# SCH_RejsaCAN_v3_4.net
KiCad netlist of a schematic drawn in EasyEDA
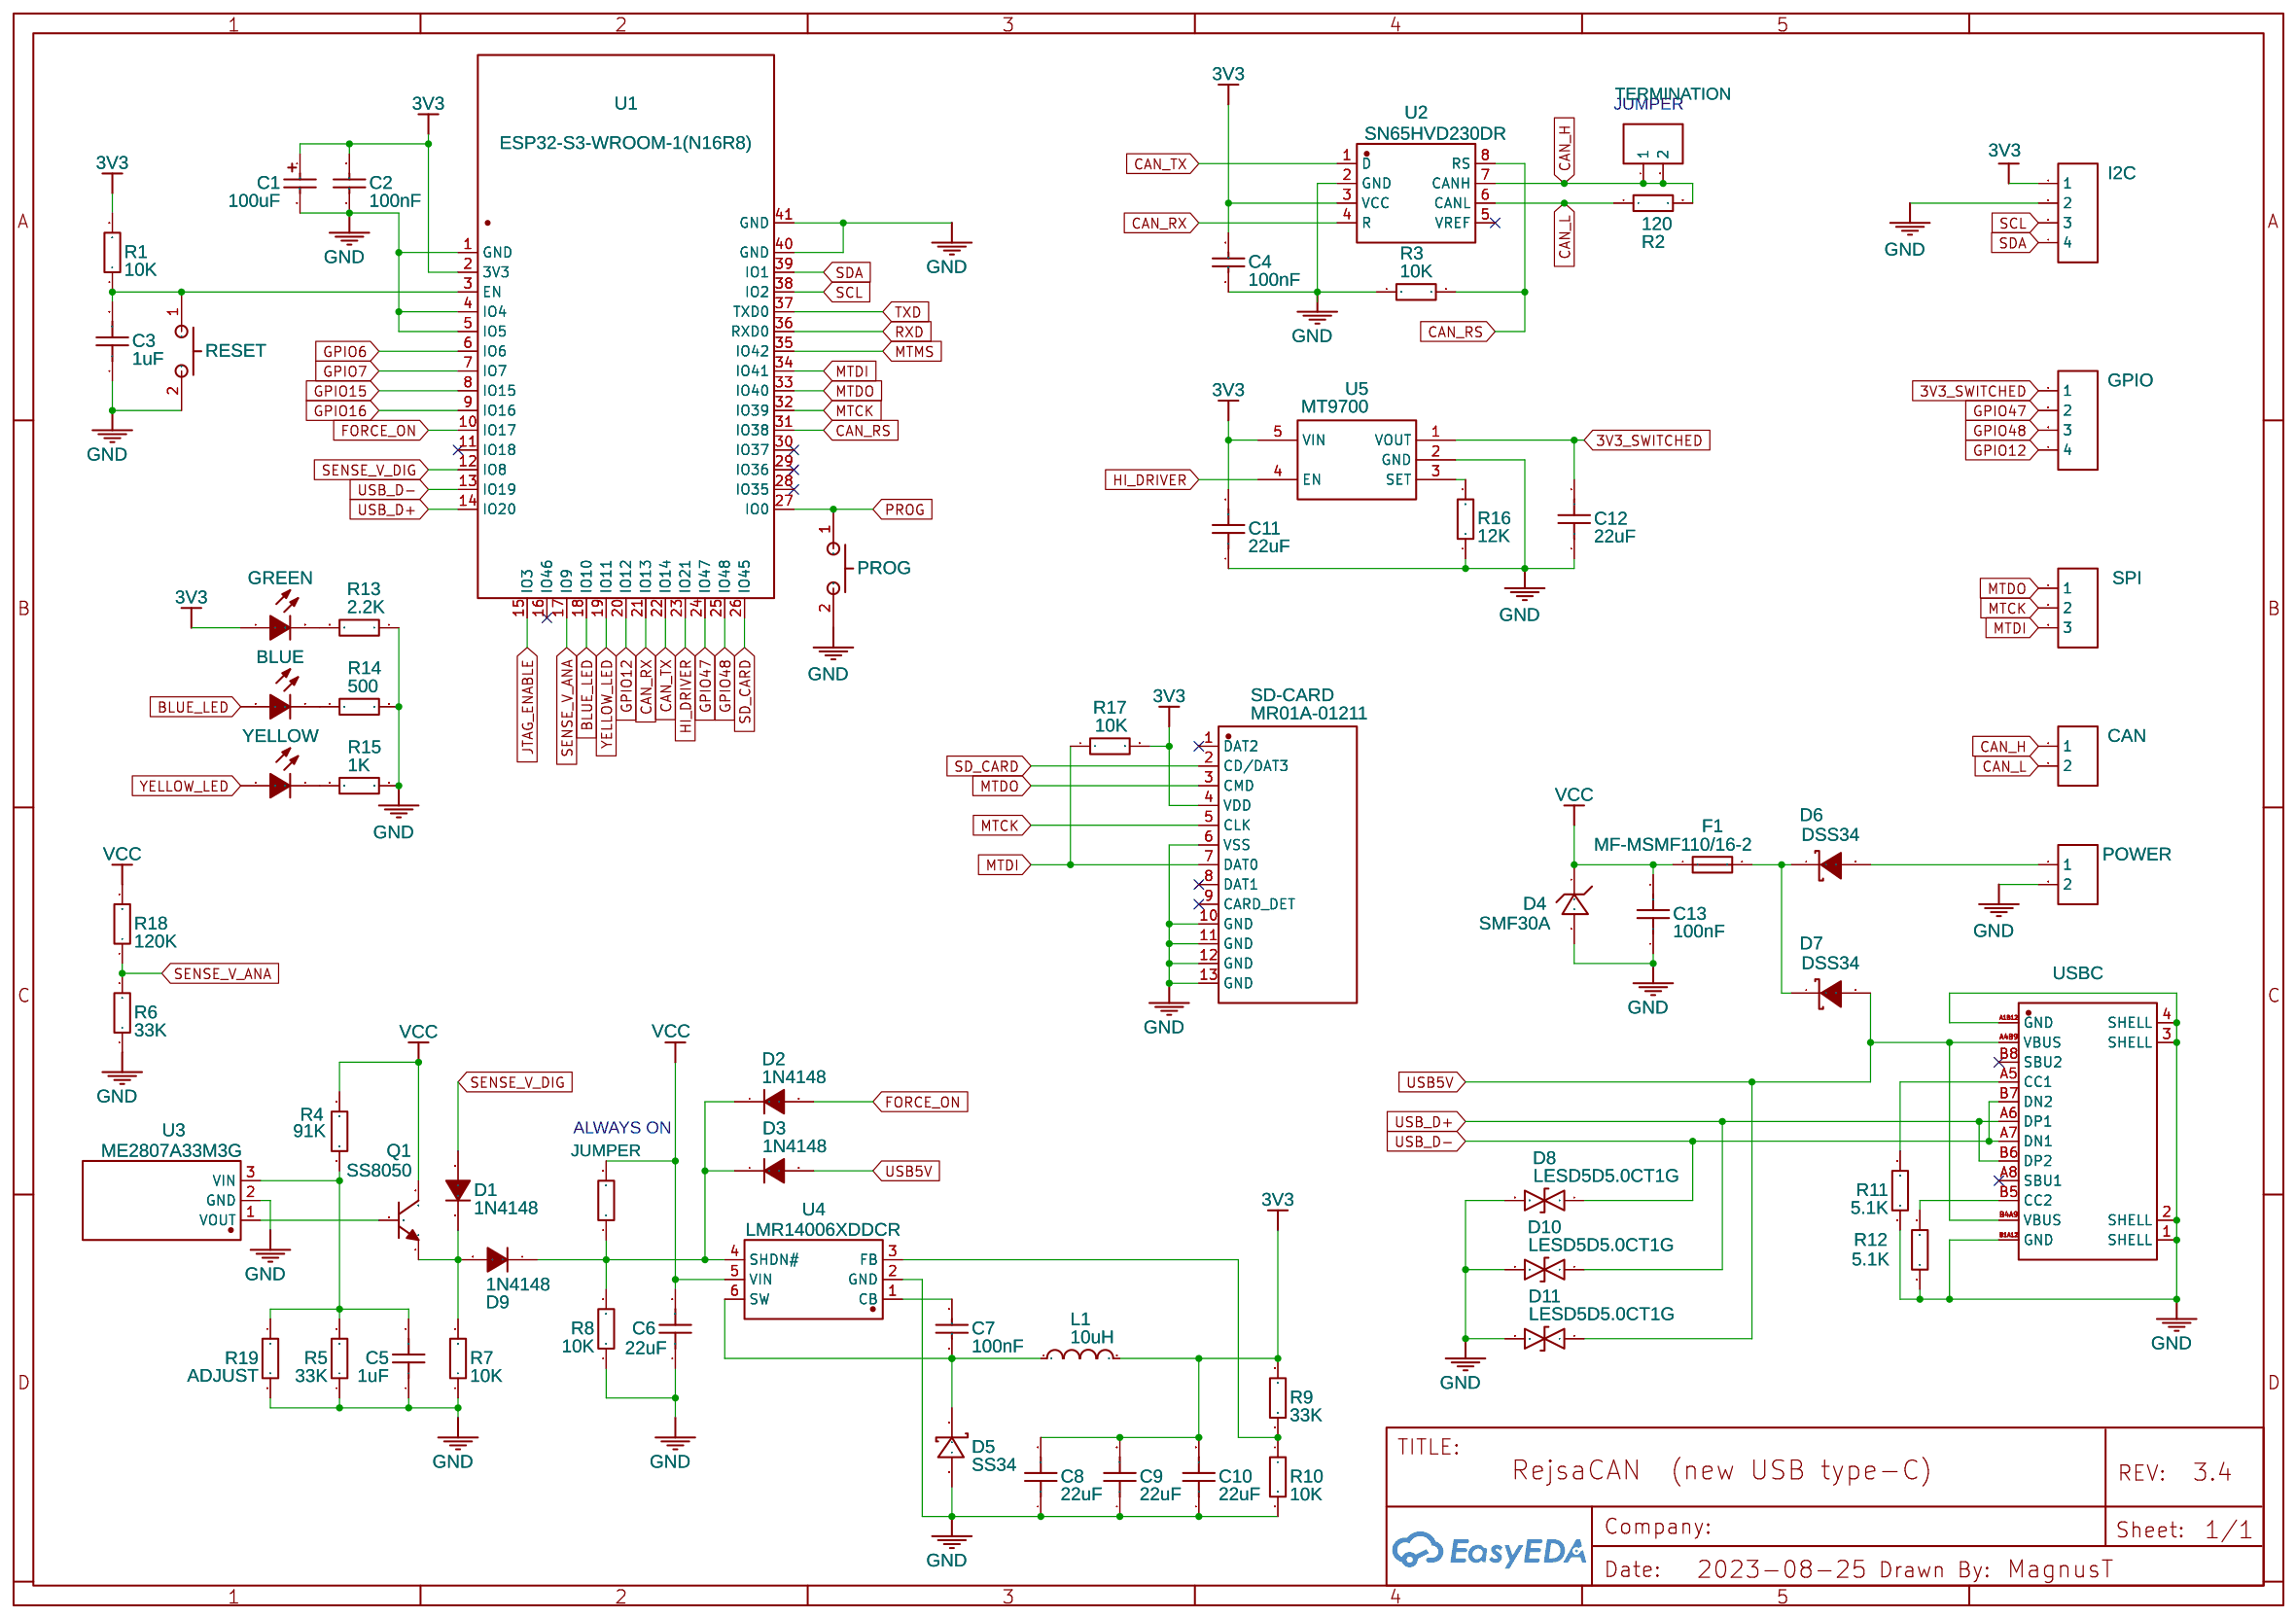
[diagram p0: schematic sheet]

(export (version "E")
  (design (tool "Eeschema 10.0.6"))
  (components
    (comp (ref "BLUE")
      (value "19-217/BHC-ZL1M2RY/3T")
      (fields (field (name "Manufacturer") "EVERLIGHT"))
      (libsource (lib "") (part "19-217/BHC-ZL1M2RY/3T"))
    )
    (comp (ref "C1")
      (value "100uF")
      (fields (field (name "Manufacturer Part") "TAJB107K006RNJ") (field (name "Manufacturer") "AVX"))
      (libsource (lib "") (part "TAJB107K006RNJ"))
    )
    (comp (ref "C2")
      (value "100nF")
      (fields (field (name "Manufacturer Part") "CL05B104KO5NNNC") (field (name "Manufacturer") "SAMSUNG"))
      (libsource (lib "") (part "CL05B104KO5NNNC"))
    )
    (comp (ref "C3")
      (value "1uF")
      (fields (field (name "Manufacturer Part") "CL05A105KA5NQNC") (field (name "Manufacturer") "SAMSUNG"))
      (libsource (lib "") (part "CL05A105KA5NQNC_1"))
    )
    (comp (ref "C4")
      (value "100nF")
      (fields (field (name "Manufacturer Part") "CL05B104KO5NNNC") (field (name "Manufacturer") "SAMSUNG"))
      (libsource (lib "") (part "CL05B104KO5NNNC"))
    )
    (comp (ref "C5")
      (value "1uF")
      (fields (field (name "Manufacturer Part") "CL05A105KA5NQNC") (field (name "Manufacturer") "SAMSUNG"))
      (libsource (lib "") (part "CL05A105KA5NQNC"))
    )
    (comp (ref "C6")
      (value "22uF")
      (fields
        (field (name "Manufacturer Part") "CL21A226MAYNNNE")
        (field (name "Manufacturer") "Samsung Electro-Mechanics")
      )
      (libsource (lib "") (part "CL21A226MAYNNNE"))
    )
    (comp (ref "C7")
      (value "100nF")
      (fields (field (name "Manufacturer Part") "CL05B104KO5NNNC") (field (name "Manufacturer") "SAMSUNG"))
      (libsource (lib "") (part "CL05B104KO5NNNC"))
    )
    (comp (ref "C8")
      (value "22uF")
      (fields (field (name "Manufacturer Part") "CL10A226MQ8NRNC") (field (name "Manufacturer") "SAMSUNG"))
      (libsource (lib "") (part "CL10A226MQ8NRNC"))
    )
    (comp (ref "C9")
      (value "22uF")
      (fields (field (name "Manufacturer Part") "CL10A226MQ8NRNC") (field (name "Manufacturer") "SAMSUNG"))
      (libsource (lib "") (part "CL10A226MQ8NRNC"))
    )
    (comp (ref "C10")
      (value "22uF")
      (fields (field (name "Manufacturer Part") "CL10A226MQ8NRNC") (field (name "Manufacturer") "SAMSUNG"))
      (libsource (lib "") (part "CL10A226MQ8NRNC"))
    )
    (comp (ref "C11")
      (value "22uF")
      (fields (field (name "Manufacturer Part") "CL10A226MQ8NRNC") (field (name "Manufacturer") "SAMSUNG"))
      (libsource (lib "") (part "CL10A226MQ8NRNC"))
    )
    (comp (ref "C12")
      (value "22uF")
      (fields (field (name "Manufacturer Part") "CL10A226MQ8NRNC") (field (name "Manufacturer") "SAMSUNG"))
      (libsource (lib "") (part "CL10A226MQ8NRNC"))
    )
    (comp (ref "C13")
      (value "100nF")
      (fields
        (field (name "Manufacturer Part") "CL05B104KB54PNC")
        (field (name "Manufacturer") "Samsung Electro-Mechanics")
      )
      (libsource (lib "") (part "CL05B104KB54PNC"))
    )
    (comp (ref "CAN") (value "HDR-M-2.54_1x2") (libsource (lib "") (part "HDR-M-2.54_1x2")))
    (comp (ref "D1")
      (value "1N4148")
      (fields (field (name "Manufacturer Part") "1N4148WS T4") (field (name "Manufacturer") "CJ"))
      (libsource (lib "") (part "1N4148WS T4_2"))
    )
    (comp (ref "D2")
      (value "1N4148")
      (fields (field (name "Manufacturer Part") "1N4148WS T4") (field (name "Manufacturer") "CJ"))
      (libsource (lib "") (part "1N4148WS T4"))
    )
    (comp (ref "D3")
      (value "1N4148")
      (fields (field (name "Manufacturer Part") "1N4148WS T4") (field (name "Manufacturer") "CJ"))
      (libsource (lib "") (part "1N4148WS T4"))
    )
    (comp (ref "D4")
      (value "SMF30A")
      (fields (field (name "Manufacturer") "DOWO"))
      (libsource (lib "") (part "SMF30A_C366558"))
    )
    (comp (ref "D5")
      (value "SS34")
      (fields (field (name "Manufacturer") "MDD"))
      (libsource (lib "") (part "SS34_C8678"))
    )
    (comp (ref "D6")
      (value "DSS34")
      (fields (field (name "Manufacturer") "STARSEA"))
      (libsource (lib "") (part "DSS34"))
    )
    (comp (ref "D7")
      (value "DSS34")
      (fields (field (name "Manufacturer") "STARSEA"))
      (libsource (lib "") (part "DSS34"))
    )
    (comp (ref "D8")
      (value "LESD5D5.0CT1G")
      (fields (field (name "Manufacturer") "Leshan Radio"))
      (libsource (lib "") (part "LESD5D5.0CT1G"))
    )
    (comp (ref "D9")
      (value "1N4148")
      (fields (field (name "Manufacturer Part") "1N4148WS T4") (field (name "Manufacturer") "CJ"))
      (libsource (lib "") (part "1N4148WS T4_1"))
    )
    (comp (ref "D10")
      (value "LESD5D5.0CT1G")
      (fields (field (name "Manufacturer") "Leshan Radio"))
      (libsource (lib "") (part "LESD5D5.0CT1G"))
    )
    (comp (ref "D11")
      (value "LESD5D5.0CT1G")
      (fields (field (name "Manufacturer") "Leshan Radio"))
      (libsource (lib "") (part "LESD5D5.0CT1G"))
    )
    (comp (ref "F1")
      (value "MF-MSMF110/16-2")
      (fields (field (name "Manufacturer") "BOURNS"))
      (libsource (lib "") (part "MF-MSMF110/16-2"))
    )
    (comp (ref "GPIO") (value "HDR-M-2.54_1x4") (libsource (lib "") (part "HDR-M-2.54_1x4_1")))
    (comp (ref "GREEN")
      (value "19-217/GHC-YR1S2/3T")
      (fields (field (name "Manufacturer") "EVERLIGHT"))
      (libsource (lib "") (part "19-217/GHC-YR1S2/3T"))
    )
    (comp (ref "I2C") (value "HDR-M-2.54_1x4") (libsource (lib "") (part "HDR-M-2.54_1x4")))
    (comp (ref "JUMPER") (value "-") (libsource (lib "") (part "0402WGF3092TCE")))
    (comp (ref "L1")
      (value "10uH")
      (fields
        (field (name "Manufacturer Part") "SLP6028S100MTT")
        (field (name "Manufacturer") "Sunltech Tech")
      )
      (libsource (lib "") (part "SLP6028S100MTT"))
    )
    (comp (ref "POWER") (value "HDR-M-2.54_1x2") (libsource (lib "") (part "HDR-M-2.54_1x2_1")))
    (comp (ref "PROG")
      (value "GT-TC029B-H025-L1N")
      (fields (field (name "Manufacturer") "G-Switch"))
      (libsource (lib "") (part "GT-TC029B-H025-L1N"))
    )
    (comp (ref "Q1")
      (value "SS8050")
      (fields (field (name "Manufacturer") "CJ"))
      (libsource (lib "") (part "SS8050_C2150"))
    )
    (comp (ref "R1")
      (value "10K")
      (fields (field (name "Manufacturer Part") "0402WGF1002TCE") (field (name "Manufacturer") "UniOhm"))
      (libsource (lib "") (part "0402WGF1002TCE_1"))
    )
    (comp (ref "R2")
      (value "120")
      (fields (field (name "Manufacturer Part") "RTT061200FTP") (field (name "Manufacturer") "RALEC"))
      (libsource (lib "") (part "RTT061200FTP"))
    )
    (comp (ref "R3")
      (value "10K")
      (fields (field (name "Manufacturer Part") "0402WGF1002TCE") (field (name "Manufacturer") "UniOhm"))
      (libsource (lib "") (part "0402WGF1002TCE"))
    )
    (comp (ref "R4")
      (value "91K")
      (fields (field (name "Manufacturer Part") "0402WGF9102TCE") (field (name "Manufacturer") "UniOhm"))
      (libsource (lib "") (part "0402WGF9102TCE"))
    )
    (comp (ref "R5")
      (value "33K")
      (fields (field (name "Manufacturer Part") "0402WGF3302TCE") (field (name "Manufacturer") "UniOhm"))
      (libsource (lib "") (part "0402WGF3302TCE"))
    )
    (comp (ref "R6")
      (value "33K")
      (fields (field (name "Manufacturer Part") "0402WGF3302TCE") (field (name "Manufacturer") "UniOhm"))
      (libsource (lib "") (part "0402WGF3302TCE"))
    )
    (comp (ref "R7")
      (value "10K")
      (fields (field (name "Manufacturer Part") "0402WGF1002TCE") (field (name "Manufacturer") "UniOhm"))
      (libsource (lib "") (part "0402WGF1002TCE_1"))
    )
    (comp (ref "R8")
      (value "10K")
      (fields (field (name "Manufacturer Part") "0402WGF1002TCE") (field (name "Manufacturer") "UniOhm"))
      (libsource (lib "") (part "0402WGF1002TCE_1"))
    )
    (comp (ref "R9")
      (value "33K")
      (fields (field (name "Manufacturer Part") "0402WGF3302TCE") (field (name "Manufacturer") "UniOhm"))
      (libsource (lib "") (part "0402WGF3302TCE"))
    )
    (comp (ref "R10")
      (value "10K")
      (fields (field (name "Manufacturer Part") "0402WGF1002TCE") (field (name "Manufacturer") "UniOhm"))
      (libsource (lib "") (part "0402WGF1002TCE_2"))
    )
    (comp (ref "R11")
      (value "5.1K")
      (fields (field (name "Manufacturer Part") "0402WGF5101TCE") (field (name "Manufacturer") "UniOhm"))
      (libsource (lib "") (part "0402WGF5101TCE"))
    )
    (comp (ref "R12")
      (value "5.1K")
      (fields (field (name "Manufacturer Part") "0402WGF5101TCE") (field (name "Manufacturer") "UniOhm"))
      (libsource (lib "") (part "0402WGF5101TCE"))
    )
    (comp (ref "R13")
      (value "2.2K")
      (fields (field (name "Manufacturer Part") "0402WGF2201TCE") (field (name "Manufacturer") "UniOhm"))
      (libsource (lib "") (part "0402WGF2201TCE"))
    )
    (comp (ref "R14")
      (value "500")
      (fields (field (name "Manufacturer Part") "0402WGF4700TCE") (field (name "Manufacturer") "UniOhm"))
      (libsource (lib "") (part "0402WGF1001TCE"))
    )
    (comp (ref "R15")
      (value "1K")
      (fields (field (name "Manufacturer Part") "0402WGF1001TCE") (field (name "Manufacturer") "UniOhm"))
      (libsource (lib "") (part "0402WGF1001TCE"))
    )
    (comp (ref "R16")
      (value "12K")
      (fields (field (name "Manufacturer Part") "0402WGF1202TCE") (field (name "Manufacturer") "UniOhm"))
      (libsource (lib "") (part "0402WGF1202TCE"))
    )
    (comp (ref "R17")
      (value "10K")
      (fields (field (name "Manufacturer Part") "0402WGF1002TCE") (field (name "Manufacturer") "UniOhm"))
      (libsource (lib "") (part "0402WGF1002TCE"))
    )
    (comp (ref "R18")
      (value "120K")
      (fields (field (name "Manufacturer Part") "0402WGF1203TCE") (field (name "Manufacturer") "UniOhm"))
      (libsource (lib "") (part "0402WGF1203TCE"))
    )
    (comp (ref "R19")
      (value "ADJUST")
      (fields (field (name "Manufacturer Part") "0402WGF9102TCE") (field (name "Manufacturer") "UniOhm"))
      (libsource (lib "") (part "0402WGF9102TCE_1"))
    )
    (comp (ref "RESET")
      (value "GT-TC029B-H025-L1N")
      (fields (field (name "Manufacturer") "G-Switch"))
      (libsource (lib "") (part "GT-TC029B-H025-L1N_1"))
    )
    (comp (ref "SD-CARD")
      (value "MR01A-01211")
      (fields (field (name "Manufacturer") "ATOM(爱特姆)"))
      (libsource (lib "") (part "MR01A-01211"))
    )
    (comp (ref "SPI") (value "HDR-M-2.54_1x3") (libsource (lib "") (part "HDR-M-2.54_1x3")))
    (comp (ref "TERMINATION") (value "HDR-M-2.54_1x2") (libsource (lib "") (part "HDR-M-2.54_1x2_2")))
    (comp (ref "U1")
      (value "ESP32-S3-WROOM-1(N16R8)")
      (fields (field (name "Manufacturer") "ESPRESSIF(乐鑫)"))
      (libsource (lib "") (part "ESP32-S3-WROOM-1(N16R8)"))
    )
    (comp (ref "U2")
      (value "SN65HVD230DR")
      (fields (field (name "Manufacturer") "TI"))
      (libsource (lib "") (part "SN65HVD230DR"))
    )
    (comp (ref "U3")
      (value "ME2807A33M3G")
      (fields (field (name "Manufacturer") "Nanjing Micro One Elec"))
      (libsource (lib "") (part "ME2807A33M3G"))
    )
    (comp (ref "U4")
      (value "LMR14006XDDCR")
      (fields (field (name "Manufacturer") "Texas Instruments"))
      (libsource (lib "") (part "LMR14006XDDCR"))
    )
    (comp (ref "U5")
      (value "MT9700")
      (fields (field (name "Manufacturer") "AEROSEMI"))
      (libsource (lib "") (part "MT9700"))
    )
    (comp (ref "USBC")
      (value "GT-USB-7010ASV")
      (fields (field (name "Manufacturer") "G-Switch(品赞)"))
      (libsource (lib "") (part "GT-USB-7010ASV"))
    )
    (comp (ref "YELLOW")
      (value "19-213/Y2C-CQ2R2L/3T(CY)")
      (fields (field (name "Manufacturer") "EVERLIGHT"))
      (libsource (lib "") (part "19-213/Y2C-CQ2R2L/3T(CY)"))
    )
  )
  (nets
    (net (code "1") (name "3V3") (class "Default")
      (node (ref "C1") (pin "1") (pinfunction "1_1") (pintype "input"))
      (node (ref "C10") (pin "2") (pinfunction "2_2") (pintype "unspecified"))
      (node (ref "C11") (pin "2") (pinfunction "2_2") (pintype "unspecified"))
      (node (ref "C2") (pin "2") (pinfunction "2_2") (pintype "input"))
      (node (ref "C4") (pin "2") (pinfunction "2_2") (pintype "input"))
      (node (ref "C8") (pin "2") (pinfunction "2_2") (pintype "unspecified"))
      (node (ref "C9") (pin "2") (pinfunction "2_2") (pintype "unspecified"))
      (node (ref "GREEN") (pin "1") (pinfunction "A_1") (pintype "input"))
      (node (ref "I2C") (pin "1") (pinfunction "1_1") (pintype "unspecified"))
      (node (ref "L1") (pin "2") (pinfunction "2_2") (pintype "unspecified"))
      (node (ref "R1") (pin "2") (pinfunction "2_2") (pintype "input"))
      (node (ref "R17") (pin "2") (pinfunction "2_2") (pintype "input"))
      (node (ref "R9") (pin "2") (pinfunction "2_2") (pintype "input"))
      (node (ref "SD-CARD") (pin "4") (pinfunction "VDD_4") (pintype "unspecified"))
      (node (ref "U1") (pin "2") (pinfunction "3V3_2") (pintype "unspecified"))
      (node (ref "U2") (pin "3") (pinfunction "VCC_3") (pintype "unspecified"))
      (node (ref "U5") (pin "5") (pinfunction "VIN_5") (pintype "unspecified"))
    )
    (net (code "2") (name "3V3_SWITCHED") (class "Default")
      (node (ref "C12") (pin "2") (pinfunction "2_2") (pintype "unspecified"))
      (node (ref "GPIO") (pin "1") (pinfunction "1_1") (pintype "unspecified"))
      (node (ref "U5") (pin "1") (pinfunction "VOUT_1") (pintype "unspecified"))
    )
    (net (code "3") (name "BLUE_LED") (class "Default")
      (node (ref "BLUE") (pin "1") (pinfunction "A_1") (pintype "input"))
      (node (ref "U1") (pin "18") (pinfunction "IO10_18") (pintype "unspecified"))
    )
    (net (code "4") (name "CAN_H") (class "Default")
      (node (ref "CAN") (pin "1") (pinfunction "1_1") (pintype "unspecified"))
      (node (ref "R2") (pin "2") (pinfunction "2_2") (pintype "unspecified"))
      (node (ref "TERMINATION") (pin "1") (pinfunction "1_1") (pintype "unspecified"))
      (node (ref "TERMINATION") (pin "2") (pinfunction "2_2") (pintype "unspecified"))
      (node (ref "U2") (pin "7") (pinfunction "CANH_7") (pintype "unspecified"))
    )
    (net (code "5") (name "CAN_L") (class "Default")
      (node (ref "CAN") (pin "2") (pinfunction "2_2") (pintype "unspecified"))
      (node (ref "R2") (pin "1") (pinfunction "1_1") (pintype "unspecified"))
      (node (ref "U2") (pin "6") (pinfunction "CANL_6") (pintype "unspecified"))
    )
    (net (code "6") (name "CAN_RS") (class "Default")
      (node (ref "R3") (pin "2") (pinfunction "2_2") (pintype "input"))
      (node (ref "U1") (pin "31") (pinfunction "IO38_31") (pintype "unspecified"))
      (node (ref "U2") (pin "8") (pinfunction "RS_8") (pintype "unspecified"))
    )
    (net (code "7") (name "CAN_RX") (class "Default")
      (node (ref "U1") (pin "21") (pinfunction "IO13_21") (pintype "unspecified"))
      (node (ref "U2") (pin "4") (pinfunction "R_4") (pintype "unspecified"))
    )
    (net (code "8") (name "CAN_TX") (class "Default")
      (node (ref "U1") (pin "22") (pinfunction "IO14_22") (pintype "unspecified"))
      (node (ref "U2") (pin "1") (pinfunction "D_1") (pintype "unspecified"))
    )
    (net (code "9") (name "FORCE_ON") (class "Default")
      (node (ref "D2") (pin "2") (pinfunction "A_2") (pintype "unspecified"))
      (node (ref "U1") (pin "10") (pinfunction "IO17_10") (pintype "unspecified"))
    )
    (net (code "10") (name "GND") (class "Default")
      (node (ref "C1") (pin "2") (pinfunction "2_2") (pintype "input"))
      (node (ref "C10") (pin "1") (pinfunction "1_1") (pintype "unspecified"))
      (node (ref "C11") (pin "1") (pinfunction "1_1") (pintype "unspecified"))
      (node (ref "C12") (pin "1") (pinfunction "1_1") (pintype "unspecified"))
      (node (ref "C13") (pin "1") (pinfunction "1_1") (pintype "unspecified"))
      (node (ref "C2") (pin "1") (pinfunction "1_1") (pintype "input"))
      (node (ref "C3") (pin "1") (pinfunction "1_1") (pintype "unspecified"))
      (node (ref "C4") (pin "1") (pinfunction "1_1") (pintype "input"))
      (node (ref "C5") (pin "1") (pinfunction "1_1") (pintype "unspecified"))
      (node (ref "C6") (pin "1") (pinfunction "1_1") (pintype "unspecified"))
      (node (ref "C8") (pin "1") (pinfunction "1_1") (pintype "unspecified"))
      (node (ref "C9") (pin "1") (pinfunction "1_1") (pintype "unspecified"))
      (node (ref "D10") (pin "2") (pinfunction "2_2") (pintype "unspecified"))
      (node (ref "D11") (pin "2") (pinfunction "2_2") (pintype "unspecified"))
      (node (ref "D4") (pin "2") (pinfunction "2_2") (pintype "unspecified"))
      (node (ref "D5") (pin "2") (pinfunction "A_2") (pintype "unspecified"))
      (node (ref "D8") (pin "2") (pinfunction "2_2") (pintype "unspecified"))
      (node (ref "I2C") (pin "2") (pinfunction "2_2") (pintype "unspecified"))
      (node (ref "POWER") (pin "2") (pinfunction "2_2") (pintype "unspecified"))
      (node (ref "PROG") (pin "2") (pinfunction "2_2") (pintype "unspecified"))
      (node (ref "R10") (pin "2") (pinfunction "2_2") (pintype "input"))
      (node (ref "R11") (pin "1") (pinfunction "1_1") (pintype "input"))
      (node (ref "R12") (pin "1") (pinfunction "1_1") (pintype "input"))
      (node (ref "R13") (pin "1") (pinfunction "1_1") (pintype "input"))
      (node (ref "R14") (pin "2") (pinfunction "2_2") (pintype "input"))
      (node (ref "R15") (pin "2") (pinfunction "2_2") (pintype "input"))
      (node (ref "R16") (pin "1") (pinfunction "1_1") (pintype "input"))
      (node (ref "R19") (pin "2") (pinfunction "2_2") (pintype "input"))
      (node (ref "R3") (pin "1") (pinfunction "1_1") (pintype "input"))
      (node (ref "R5") (pin "1") (pinfunction "1_1") (pintype "input"))
      (node (ref "R6") (pin "1") (pinfunction "1_1") (pintype "input"))
      (node (ref "R7") (pin "1") (pinfunction "1_1") (pintype "input"))
      (node (ref "R8") (pin "1") (pinfunction "1_1") (pintype "input"))
      (node (ref "RESET") (pin "2") (pinfunction "2_2") (pintype "unspecified"))
      (node (ref "SD-CARD") (pin "10") (pinfunction "GND_10") (pintype "unspecified"))
      (node (ref "SD-CARD") (pin "11") (pinfunction "GND_11") (pintype "unspecified"))
      (node (ref "SD-CARD") (pin "12") (pinfunction "GND_12") (pintype "unspecified"))
      (node (ref "SD-CARD") (pin "13") (pinfunction "GND_13") (pintype "unspecified"))
      (node (ref "SD-CARD") (pin "6") (pinfunction "VSS_6") (pintype "unspecified"))
      (node (ref "U1") (pin "1") (pinfunction "GND_1") (pintype "unspecified"))
      (node (ref "U1") (pin "4") (pinfunction "IO4_4") (pintype "unspecified"))
      (node (ref "U1") (pin "40") (pinfunction "GND_40") (pintype "unspecified"))
      (node (ref "U1") (pin "41") (pinfunction "GND_41") (pintype "unspecified"))
      (node (ref "U1") (pin "5") (pinfunction "IO5_5") (pintype "unspecified"))
      (node (ref "U2") (pin "2") (pinfunction "GND_2") (pintype "unspecified"))
      (node (ref "U3") (pin "2") (pinfunction "GND_2") (pintype "unspecified"))
      (node (ref "U4") (pin "2") (pinfunction "GND_2") (pintype "unspecified"))
      (node (ref "U5") (pin "2") (pinfunction "GND_2") (pintype "unspecified"))
      (node (ref "USBC") (pin "1") (pinfunction "SHELL_1") (pintype "unspecified"))
      (node (ref "USBC") (pin "2") (pinfunction "SHELL_2") (pintype "unspecified"))
      (node (ref "USBC") (pin "3") (pinfunction "SHELL_3") (pintype "unspecified"))
      (node (ref "USBC") (pin "4") (pinfunction "SHELL_4") (pintype "unspecified"))
      (node (ref "USBC") (pin "A1B12") (pinfunction "GND_A1B12") (pintype "unspecified"))
      (node (ref "USBC") (pin "B1A12") (pinfunction "GND_B1A12") (pintype "unspecified"))
    )
    (net (code "11") (name "GPIO6") (class "Default")
      (node (ref "U1") (pin "6") (pinfunction "IO6_6") (pintype "unspecified"))
    )
    (net (code "12") (name "GPIO7") (class "Default")
      (node (ref "U1") (pin "7") (pinfunction "IO7_7") (pintype "unspecified"))
    )
    (net (code "13") (name "GPIO12") (class "Default")
      (node (ref "GPIO") (pin "4") (pinfunction "4_4") (pintype "unspecified"))
      (node (ref "U1") (pin "20") (pinfunction "IO12_20") (pintype "unspecified"))
    )
    (net (code "14") (name "GPIO15") (class "Default")
      (node (ref "U1") (pin "8") (pinfunction "IO15_8") (pintype "unspecified"))
    )
    (net (code "15") (name "GPIO16") (class "Default")
      (node (ref "U1") (pin "9") (pinfunction "IO16_9") (pintype "unspecified"))
    )
    (net (code "16") (name "GPIO47") (class "Default")
      (node (ref "GPIO") (pin "2") (pinfunction "2_2") (pintype "unspecified"))
      (node (ref "U1") (pin "24") (pinfunction "IO47_24") (pintype "unspecified"))
    )
    (net (code "17") (name "GPIO48") (class "Default")
      (node (ref "GPIO") (pin "3") (pinfunction "3_3") (pintype "unspecified"))
      (node (ref "U1") (pin "25") (pinfunction "IO48_25") (pintype "unspecified"))
    )
    (net (code "18") (name "HI_DRIVER") (class "Default")
      (node (ref "U1") (pin "23") (pinfunction "IO21_23") (pintype "unspecified"))
      (node (ref "U5") (pin "4") (pinfunction "EN_4") (pintype "unspecified"))
    )
    (net (code "19") (name "JTAG_ENABLE") (class "Default")
      (node (ref "U1") (pin "15") (pinfunction "IO3_15") (pintype "unspecified"))
    )
    (net (code "20") (name "MTCK") (class "Default")
      (node (ref "SD-CARD") (pin "5") (pinfunction "CLK_5") (pintype "unspecified"))
      (node (ref "SPI") (pin "2") (pinfunction "2_2") (pintype "input"))
      (node (ref "U1") (pin "32") (pinfunction "IO39_32") (pintype "unspecified"))
    )
    (net (code "21") (name "MTDI") (class "Default")
      (node (ref "R17") (pin "1") (pinfunction "1_1") (pintype "input"))
      (node (ref "SD-CARD") (pin "7") (pinfunction "DAT0_7") (pintype "unspecified"))
      (node (ref "SPI") (pin "3") (pinfunction "3_3") (pintype "input"))
      (node (ref "U1") (pin "34") (pinfunction "IO41_34") (pintype "unspecified"))
    )
    (net (code "22") (name "MTDO") (class "Default")
      (node (ref "SD-CARD") (pin "3") (pinfunction "CMD_3") (pintype "unspecified"))
      (node (ref "SPI") (pin "1") (pinfunction "1_1") (pintype "input"))
      (node (ref "U1") (pin "33") (pinfunction "IO40_33") (pintype "unspecified"))
    )
    (net (code "23") (name "MTMS") (class "Default")
      (node (ref "U1") (pin "35") (pinfunction "IO42_35") (pintype "unspecified"))
    )
    (net (code "24") (name "Net-(BLUE-C)") (class "Default")
      (node (ref "BLUE") (pin "2") (pinfunction "C_2") (pintype "input"))
      (node (ref "R14") (pin "1") (pinfunction "1_1") (pintype "input"))
    )
    (net (code "25") (name "Net-(D1-K)") (class "Default")
      (node (ref "D1") (pin "1") (pinfunction "K_1") (pintype "unspecified"))
      (node (ref "D9") (pin "2") (pinfunction "A_2") (pintype "unspecified"))
      (node (ref "Q1") (pin "2") (pinfunction "E_2") (pintype "unspecified"))
      (node (ref "R7") (pin "2") (pinfunction "2_2") (pintype "input"))
    )
    (net (code "26") (name "Net-(D2-K)") (class "Default")
      (node (ref "D2") (pin "1") (pinfunction "K_1") (pintype "unspecified"))
      (node (ref "D3") (pin "1") (pinfunction "K_1") (pintype "unspecified"))
      (node (ref "D9") (pin "1") (pinfunction "K_1") (pintype "unspecified"))
      (node (ref "JUMPER") (pin "1") (pinfunction "1_1") (pintype "unspecified"))
      (node (ref "R8") (pin "2") (pinfunction "2_2") (pintype "input"))
      (node (ref "U4") (pin "4") (pinfunction "SHDN#_4") (pintype "unspecified"))
    )
    (net (code "27") (name "Net-(D5-K)") (class "Default")
      (node (ref "C7") (pin "1") (pinfunction "1_1") (pintype "input"))
      (node (ref "D5") (pin "1") (pinfunction "K_1") (pintype "unspecified"))
      (node (ref "L1") (pin "1") (pinfunction "1_1") (pintype "unspecified"))
      (node (ref "U4") (pin "6") (pinfunction "SW_6") (pintype "unspecified"))
    )
    (net (code "28") (name "Net-(D6-A)") (class "Default")
      (node (ref "D6") (pin "2") (pinfunction "A_2") (pintype "unspecified"))
      (node (ref "POWER") (pin "1") (pinfunction "1_1") (pintype "unspecified"))
    )
    (net (code "29") (name "Net-(D6-K)") (class "Default")
      (node (ref "D6") (pin "1") (pinfunction "K_1") (pintype "unspecified"))
      (node (ref "D7") (pin "1") (pinfunction "K_1") (pintype "unspecified"))
      (node (ref "F1") (pin "2") (pinfunction "2_2") (pintype "unspecified"))
    )
    (net (code "30") (name "Net-(GREEN-C)") (class "Default")
      (node (ref "GREEN") (pin "2") (pinfunction "C_2") (pintype "input"))
      (node (ref "R13") (pin "2") (pinfunction "2_2") (pintype "input"))
    )
    (net (code "31") (name "Net-(Q1-B)") (class "Default")
      (node (ref "Q1") (pin "1") (pinfunction "B_1") (pintype "unspecified"))
      (node (ref "U3") (pin "1") (pinfunction "VOUT_1") (pintype "unspecified"))
    )
    (net (code "32") (name "Net-(U1-EN)") (class "Default")
      (node (ref "C3") (pin "2") (pinfunction "2_2") (pintype "unspecified"))
      (node (ref "R1") (pin "1") (pinfunction "1_1") (pintype "input"))
      (node (ref "RESET") (pin "1") (pinfunction "1_1") (pintype "unspecified"))
      (node (ref "U1") (pin "3") (pinfunction "EN_3") (pintype "unspecified"))
    )
    (net (code "33") (name "Net-(U3-VIN)") (class "Default")
      (node (ref "C5") (pin "2") (pinfunction "2_2") (pintype "unspecified"))
      (node (ref "R19") (pin "1") (pinfunction "1_1") (pintype "input"))
      (node (ref "R4") (pin "1") (pinfunction "1_1") (pintype "input"))
      (node (ref "R5") (pin "2") (pinfunction "2_2") (pintype "input"))
      (node (ref "U3") (pin "3") (pinfunction "VIN_3") (pintype "unspecified"))
    )
    (net (code "34") (name "Net-(U4-CB)") (class "Default")
      (node (ref "C7") (pin "2") (pinfunction "2_2") (pintype "input"))
      (node (ref "U4") (pin "1") (pinfunction "CB_1") (pintype "unspecified"))
    )
    (net (code "35") (name "Net-(U4-FB)") (class "Default")
      (node (ref "R10") (pin "1") (pinfunction "1_1") (pintype "input"))
      (node (ref "R9") (pin "1") (pinfunction "1_1") (pintype "input"))
      (node (ref "U4") (pin "3") (pinfunction "FB_3") (pintype "unspecified"))
    )
    (net (code "36") (name "Net-(U5-SET)") (class "Default")
      (node (ref "R16") (pin "2") (pinfunction "2_2") (pintype "input"))
      (node (ref "U5") (pin "3") (pinfunction "SET_3") (pintype "unspecified"))
    )
    (net (code "37") (name "Net-(USBC-CC1)") (class "Default")
      (node (ref "R11") (pin "2") (pinfunction "2_2") (pintype "input"))
      (node (ref "USBC") (pin "A5") (pinfunction "CC1_A5") (pintype "unspecified"))
    )
    (net (code "38") (name "Net-(USBC-CC2)") (class "Default")
      (node (ref "R12") (pin "2") (pinfunction "2_2") (pintype "input"))
      (node (ref "USBC") (pin "B5") (pinfunction "CC2_B5") (pintype "unspecified"))
    )
    (net (code "39") (name "Net-(YELLOW-C)") (class "Default")
      (node (ref "R15") (pin "1") (pinfunction "1_1") (pintype "input"))
      (node (ref "YELLOW") (pin "2") (pinfunction "C_2") (pintype "input"))
    )
    (net (code "40") (name "PROG") (class "Default")
      (node (ref "PROG") (pin "1") (pinfunction "1_1") (pintype "unspecified"))
      (node (ref "U1") (pin "27") (pinfunction "IO0_27") (pintype "unspecified"))
    )
    (net (code "41") (name "RXD") (class "Default")
      (node (ref "U1") (pin "36") (pinfunction "RXD0_36") (pintype "unspecified"))
    )
    (net (code "42") (name "SCL") (class "Default")
      (node (ref "I2C") (pin "3") (pinfunction "3_3") (pintype "unspecified"))
      (node (ref "U1") (pin "38") (pinfunction "IO2_38") (pintype "unspecified"))
    )
    (net (code "43") (name "SDA") (class "Default")
      (node (ref "I2C") (pin "4") (pinfunction "4_4") (pintype "unspecified"))
      (node (ref "U1") (pin "39") (pinfunction "IO1_39") (pintype "unspecified"))
    )
    (net (code "44") (name "SD_CARD") (class "Default")
      (node (ref "SD-CARD") (pin "2") (pinfunction "CD/DAT3_2") (pintype "unspecified"))
      (node (ref "U1") (pin "26") (pinfunction "IO45_26") (pintype "unspecified"))
    )
    (net (code "45") (name "SENSE_V_ANA") (class "Default")
      (node (ref "R18") (pin "1") (pinfunction "1_1") (pintype "input"))
      (node (ref "R6") (pin "2") (pinfunction "2_2") (pintype "input"))
      (node (ref "U1") (pin "17") (pinfunction "IO9_17") (pintype "unspecified"))
    )
    (net (code "46") (name "SENSE_V_DIG") (class "Default")
      (node (ref "D1") (pin "2") (pinfunction "A_2") (pintype "unspecified"))
      (node (ref "U1") (pin "12") (pinfunction "IO8_12") (pintype "unspecified"))
    )
    (net (code "47") (name "TXD") (class "Default")
      (node (ref "U1") (pin "37") (pinfunction "TXD0_37") (pintype "unspecified"))
    )
    (net (code "48") (name "USB5V") (class "Default")
      (node (ref "D11") (pin "1") (pinfunction "1_1") (pintype "unspecified"))
      (node (ref "D3") (pin "2") (pinfunction "A_2") (pintype "unspecified"))
      (node (ref "D7") (pin "2") (pinfunction "A_2") (pintype "unspecified"))
      (node (ref "USBC") (pin "A4B9") (pinfunction "VBUS_A4B9") (pintype "unspecified"))
      (node (ref "USBC") (pin "B4A9") (pinfunction "VBUS_B4A9") (pintype "unspecified"))
    )
    (net (code "49") (name "USB_D+") (class "Default")
      (node (ref "D10") (pin "1") (pinfunction "1_1") (pintype "unspecified"))
      (node (ref "U1") (pin "14") (pinfunction "IO20_14") (pintype "unspecified"))
      (node (ref "USBC") (pin "A6") (pinfunction "DP1_A6") (pintype "unspecified"))
      (node (ref "USBC") (pin "B6") (pinfunction "DP2_B6") (pintype "unspecified"))
    )
    (net (code "50") (name "USB_D-") (class "Default")
      (node (ref "D8") (pin "1") (pinfunction "1_1") (pintype "unspecified"))
      (node (ref "U1") (pin "13") (pinfunction "IO19_13") (pintype "unspecified"))
      (node (ref "USBC") (pin "A7") (pinfunction "DN1_A7") (pintype "unspecified"))
      (node (ref "USBC") (pin "B7") (pinfunction "DN2_B7") (pintype "unspecified"))
    )
    (net (code "51") (name "VCC") (class "Default")
      (node (ref "C13") (pin "2") (pinfunction "2_2") (pintype "unspecified"))
      (node (ref "C6") (pin "2") (pinfunction "2_2") (pintype "unspecified"))
      (node (ref "D4") (pin "1") (pinfunction "1_1") (pintype "unspecified"))
      (node (ref "F1") (pin "1") (pinfunction "1_1") (pintype "unspecified"))
      (node (ref "JUMPER") (pin "2") (pinfunction "2_2") (pintype "unspecified"))
      (node (ref "Q1") (pin "3") (pinfunction "C_3") (pintype "unspecified"))
      (node (ref "R18") (pin "2") (pinfunction "2_2") (pintype "input"))
      (node (ref "R4") (pin "2") (pinfunction "2_2") (pintype "input"))
      (node (ref "U4") (pin "5") (pinfunction "VIN_5") (pintype "unspecified"))
    )
    (net (code "52") (name "YELLOW_LED") (class "Default")
      (node (ref "U1") (pin "19") (pinfunction "IO11_19") (pintype "unspecified"))
      (node (ref "YELLOW") (pin "1") (pinfunction "A_1") (pintype "input"))
    )
    (net (code "53") (name "unconnected-(SD-CARD-CARD_DET-Pad9)") (class "Default")
      (node (ref "SD-CARD") (pin "9") (pinfunction "CARD_DET_9") (pintype "unspecified+no_connect"))
    )
    (net (code "54") (name "unconnected-(SD-CARD-DAT1-Pad8)") (class "Default")
      (node (ref "SD-CARD") (pin "8") (pinfunction "DAT1_8") (pintype "unspecified+no_connect"))
    )
    (net (code "55") (name "unconnected-(SD-CARD-DAT2-Pad1)") (class "Default")
      (node (ref "SD-CARD") (pin "1") (pinfunction "DAT2_1") (pintype "unspecified+no_connect"))
    )
    (net (code "56") (name "unconnected-(U1-IO18-Pad11)") (class "Default")
      (node (ref "U1") (pin "11") (pinfunction "IO18_11") (pintype "unspecified+no_connect"))
    )
    (net (code "57") (name "unconnected-(U1-IO35-Pad28)") (class "Default")
      (node (ref "U1") (pin "28") (pinfunction "IO35_28") (pintype "unspecified+no_connect"))
    )
    (net (code "58") (name "unconnected-(U1-IO36-Pad29)") (class "Default")
      (node (ref "U1") (pin "29") (pinfunction "IO36_29") (pintype "unspecified+no_connect"))
    )
    (net (code "59") (name "unconnected-(U1-IO37-Pad30)") (class "Default")
      (node (ref "U1") (pin "30") (pinfunction "IO37_30") (pintype "unspecified+no_connect"))
    )
    (net (code "60") (name "unconnected-(U1-IO46-Pad16)") (class "Default")
      (node (ref "U1") (pin "16") (pinfunction "IO46_16") (pintype "unspecified+no_connect"))
    )
    (net (code "61") (name "unconnected-(U2-VREF-Pad5)") (class "Default")
      (node (ref "U2") (pin "5") (pinfunction "VREF_5") (pintype "unspecified+no_connect"))
    )
    (net (code "62") (name "unconnected-(USBC-SBU1-PadA8)") (class "Default")
      (node (ref "USBC") (pin "A8") (pinfunction "SBU1_A8") (pintype "unspecified+no_connect"))
    )
    (net (code "63") (name "unconnected-(USBC-SBU2-PadB8)") (class "Default")
      (node (ref "USBC") (pin "B8") (pinfunction "SBU2_B8") (pintype "unspecified+no_connect"))
    )
  )
)
